# tick-ref-gps-main.net
KiCad netlist of a schematic drawn in EAGLE
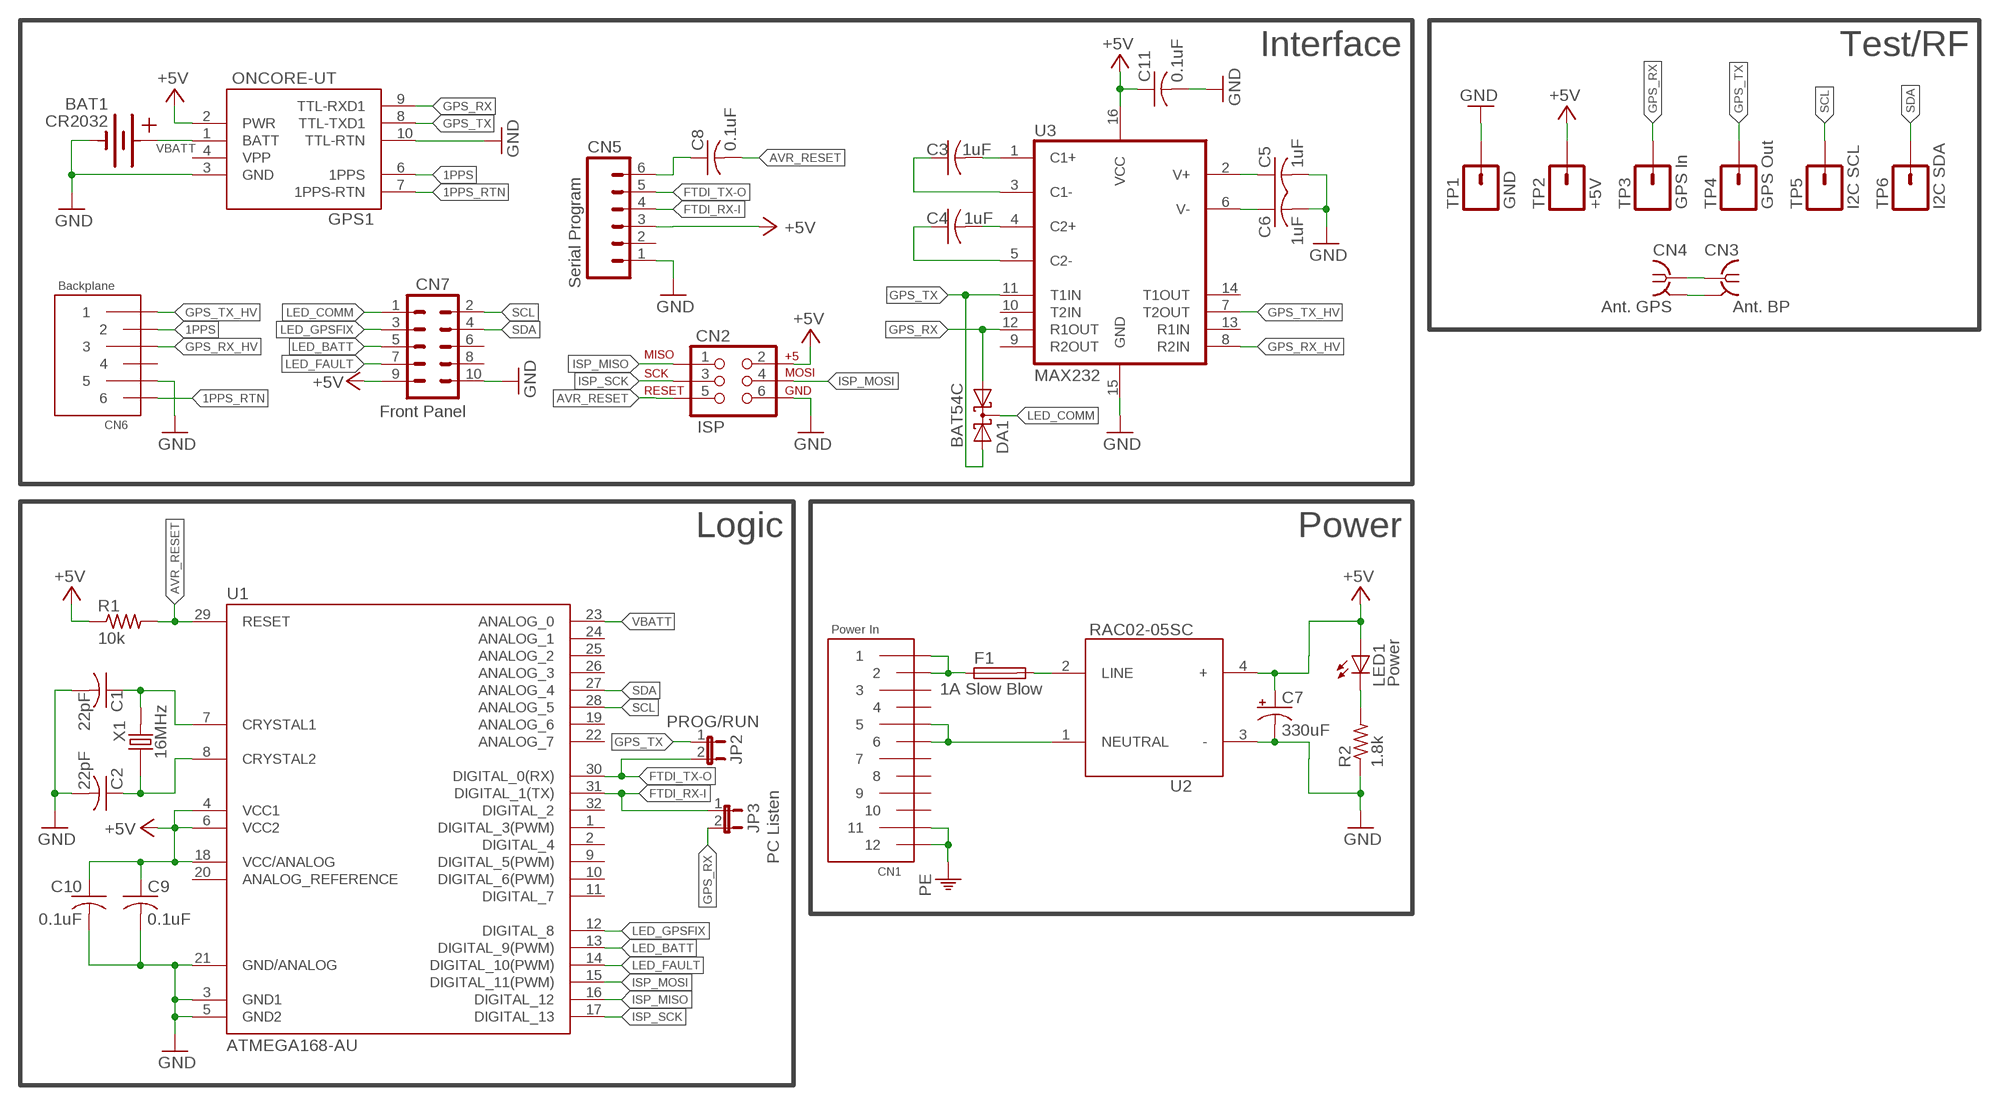
[diagram p0: schematic, sheet 1]

(export (version "E")
  (design (tool "Eeschema 10.0.6"))
  (components
    (comp (ref "BAT1")
      (value "CR2032")
      (footprint "eagle-import:BK-912-CR2032")
      (libsource (lib "eagle-import") (part "CR2032"))
    )
    (comp (ref "C1")
      (value "22pF")
      (footprint "eagle-import:C0603")
      (libsource (lib "eagle-import") (part "C-USC0603"))
    )
    (comp (ref "C2")
      (value "22pF")
      (footprint "eagle-import:C0603")
      (libsource (lib "eagle-import") (part "C-USC0603"))
    )
    (comp (ref "C3")
      (value "1uF")
      (footprint "eagle-import:C0603")
      (libsource (lib "eagle-import") (part "C-USC0603"))
    )
    (comp (ref "C4")
      (value "1uF")
      (footprint "eagle-import:C0603")
      (libsource (lib "eagle-import") (part "C-USC0603"))
    )
    (comp (ref "C5")
      (value "1uF")
      (footprint "eagle-import:C0603")
      (libsource (lib "eagle-import") (part "C-USC0603"))
    )
    (comp (ref "C6")
      (value "1uF")
      (footprint "eagle-import:C0603")
      (libsource (lib "eagle-import") (part "C-USC0603"))
    )
    (comp (ref "C7")
      (value "330uF")
      (footprint "eagle-import:E5-10,5")
      (libsource (lib "eagle-import") (part "CPOL-USE5-10.5"))
    )
    (comp (ref "C8")
      (value "0.1uF")
      (footprint "eagle-import:C0603")
      (libsource (lib "eagle-import") (part "C-USC0603"))
    )
    (comp (ref "C9")
      (value "0.1uF")
      (footprint "eagle-import:C0603")
      (libsource (lib "eagle-import") (part "C-USC0603"))
    )
    (comp (ref "C10")
      (value "0.1uF")
      (footprint "eagle-import:C0603")
      (libsource (lib "eagle-import") (part "C-USC0603"))
    )
    (comp (ref "C11")
      (value "0.1uF")
      (footprint "eagle-import:C0603")
      (libsource (lib "eagle-import") (part "C-USC0603"))
    )
    (comp (ref "CN1")
      (value "Power In")
      (footprint "eagle-import:EDGECON-M-0.15-12")
      (libsource (lib "eagle-import") (part "EDGECON-M-0.15-12"))
    )
    (comp (ref "CN2")
      (value "ISP")
      (footprint "eagle-import:2X3_LOCK")
      (libsource (lib "eagle-import") (part "AVR_SPI_PRG_62X3_LOCK"))
    )
    (comp (ref "CN3")
      (value "Ant. BP")
      (footprint "eagle-import:MMCX-J-P-X-ST-EM1-MKT")
      (libsource (lib "eagle-import") (part "COAX"))
    )
    (comp (ref "CN4")
      (value "Ant. GPS")
      (footprint "eagle-import:MOLEX-MCX-V")
      (libsource (lib "eagle-import") (part "MOLEX-MCX-V"))
    )
    (comp (ref "CN5")
      (value "Serial Program")
      (footprint "eagle-import:1X06_LOCK")
      (libsource (lib "eagle-import") (part "M06LOCK"))
    )
    (comp (ref "CN6")
      (value "Backplane")
      (footprint "eagle-import:EDGECON-M-0.1-6")
      (libsource (lib "eagle-import") (part "EDGECON-M-0.1-6"))
    )
    (comp (ref "CN7")
      (value "Front Panel")
      (footprint "eagle-import:AVR_ICSP")
      (libsource (lib "eagle-import") (part "M05X2PTH"))
    )
    (comp (ref "DA1")
      (value "BAT54C")
      (footprint "eagle-import:SOT23")
      (libsource (lib "eagle-import") (part "BAT54C"))
    )
    (comp (ref "F1")
      (value "1A Slow Blow")
      (footprint "eagle-import:SH22,5A")
      (fields (field (name "MPN") "0031.7701.11"))
      (libsource (lib "eagle-import") (part "SH22,5A"))
    )
    (comp (ref "GPS1")
      (value "ONCORE-UT")
      (footprint "eagle-import:ONCORE-UT")
      (libsource (lib "eagle-import") (part "ONCORE-UT"))
    )
    (comp (ref "JP2")
      (value "PROG/RUN")
      (footprint "eagle-import:1X02_LOCK")
      (libsource (lib "eagle-import") (part "JUMPER-2PTH_LOCK"))
    )
    (comp (ref "JP3")
      (value "PC Listen")
      (footprint "eagle-import:SJ_2S-NO")
      (libsource (lib "eagle-import") (part "JUMPER-2SMD-NO"))
    )
    (comp (ref "LED1")
      (value "Power")
      (footprint "eagle-import:CHIP-LED0603")
      (libsource (lib "eagle-import") (part "LEDCHIP-LED0603"))
    )
    (comp (ref "R1")
      (value "10k")
      (footprint "eagle-import:R0603")
      (libsource (lib "eagle-import") (part "R-US_R0603"))
    )
    (comp (ref "R2")
      (value "1.8k")
      (footprint "eagle-import:R0603")
      (libsource (lib "eagle-import") (part "R-US_R0603"))
    )
    (comp (ref "TP1")
      (value "GND")
      (footprint "eagle-import:1X01")
      (libsource (lib "eagle-import") (part "M01PTH"))
    )
    (comp (ref "TP2")
      (value "+5V")
      (footprint "eagle-import:1X01")
      (libsource (lib "eagle-import") (part "M01PTH"))
    )
    (comp (ref "TP3")
      (value "GPS In")
      (footprint "eagle-import:1X01")
      (libsource (lib "eagle-import") (part "M01PTH"))
    )
    (comp (ref "TP4")
      (value "GPS Out")
      (footprint "eagle-import:1X01")
      (libsource (lib "eagle-import") (part "M01PTH"))
    )
    (comp (ref "TP5")
      (value "I2C SCL")
      (footprint "eagle-import:1X01")
      (libsource (lib "eagle-import") (part "M01PTH"))
    )
    (comp (ref "TP6")
      (value "I2C SDA")
      (footprint "eagle-import:1X01")
      (libsource (lib "eagle-import") (part "M01PTH"))
    )
    (comp (ref "U1")
      (value "ATMEGA168-AU")
      (footprint "eagle-import:TQFP32-08")
      (libsource (lib "eagle-import") (part "ATMEGA168-AU"))
    )
    (comp (ref "U2")
      (value "RAC02-05SC")
      (footprint "eagle-import:RAC0X-SC")
      (libsource (lib "eagle-import") (part "RAC0X-SC"))
    )
    (comp (ref "U3")
      (value "MAX232")
      (footprint "eagle-import:SO016")
      (libsource (lib "eagle-import") (part "MAX232SOIC16"))
    )
    (comp (ref "X1")
      (value "16MHz")
      (footprint "eagle-import:NX5032GA")
      (libsource (lib "eagle-import") (part "NX5032GA"))
    )
  )
  (nets
    (net (code "1") (name "+5V") (class "Default")
      (node (ref "C10") (pin "1") (pinfunction "1_1") (pintype "passive"))
      (node (ref "C11") (pin "1") (pinfunction "1_1") (pintype "passive"))
      (node (ref "C7") (pin "+") (pinfunction "+_+") (pintype "passive"))
      (node (ref "C9") (pin "1") (pinfunction "1_1") (pintype "passive"))
      (node (ref "CN2") (pin "2") (pinfunction "2_2") (pintype "passive"))
      (node (ref "CN5") (pin "3") (pinfunction "3_3") (pintype "passive"))
      (node (ref "CN7") (pin "9") (pinfunction "9_9") (pintype "passive"))
      (node (ref "GPS1") (pin "2") (pinfunction "PWR_2") (pintype "power_in"))
      (node (ref "LED1") (pin "A") (pinfunction "A_A") (pintype "passive"))
      (node (ref "R1") (pin "1") (pinfunction "1_1") (pintype "passive"))
      (node (ref "TP2") (pin "1") (pinfunction "1_1") (pintype "passive"))
      (node (ref "U1") (pin "18") (pinfunction "VCC/ANALOG_18") (pintype "passive"))
      (node (ref "U1") (pin "4") (pinfunction "VCC1_4") (pintype "power_in"))
      (node (ref "U1") (pin "6") (pinfunction "VCC2_6") (pintype "power_in"))
      (node (ref "U2") (pin "4") (pinfunction "+_4") (pintype "power_in"))
      (node (ref "U3") (pin "16") (pinfunction "VCC_16") (pintype "bidirectional"))
    )
    (net (code "2") (name "/VPP") (class "Default")
      (node (ref "GPS1") (pin "4") (pinfunction "VPP_4") (pintype "power_in"))
    )
    (net (code "3") (name "1PPS") (class "Default")
      (node (ref "CN6") (pin "2") (pinfunction "2_2") (pintype "bidirectional"))
      (node (ref "GPS1") (pin "6") (pinfunction "1PPS_6") (pintype "output"))
    )
    (net (code "4") (name "1PPS_RTN") (class "Default")
      (node (ref "CN6") (pin "6") (pinfunction "6_6") (pintype "bidirectional"))
      (node (ref "GPS1") (pin "7") (pinfunction "1PPS-RTN_7") (pintype "power_in"))
    )
    (net (code "5") (name "AVR_RESET") (class "Default")
      (node (ref "C8") (pin "2") (pinfunction "2_2") (pintype "passive"))
      (node (ref "CN2") (pin "5") (pinfunction "5_5") (pintype "passive"))
      (node (ref "R1") (pin "2") (pinfunction "2_2") (pintype "passive"))
      (node (ref "U1") (pin "29") (pinfunction "RESET_29") (pintype "bidirectional"))
    )
    (net (code "6") (name "FTDI_RX-I") (class "Default")
      (node (ref "CN5") (pin "4") (pinfunction "4_4") (pintype "passive"))
      (node (ref "JP3") (pin "1") (pinfunction "1_1") (pintype "passive"))
      (node (ref "U1") (pin "31") (pinfunction "DIGITAL_1(TX)_31") (pintype "bidirectional"))
    )
    (net (code "7") (name "FTDI_TX-O") (class "Default")
      (node (ref "CN5") (pin "5") (pinfunction "5_5") (pintype "passive"))
      (node (ref "JP2") (pin "2") (pinfunction "2_2") (pintype "passive"))
      (node (ref "U1") (pin "30") (pinfunction "DIGITAL_0(RX)_30") (pintype "bidirectional"))
    )
    (net (code "8") (name "GND") (class "Default")
      (node (ref "BAT1") (pin "-") (pinfunction "-1_-") (pintype "power_in"))
      (node (ref "C1") (pin "2") (pinfunction "2_2") (pintype "passive"))
      (node (ref "C10") (pin "2") (pinfunction "2_2") (pintype "passive"))
      (node (ref "C11") (pin "2") (pinfunction "2_2") (pintype "passive"))
      (node (ref "C2") (pin "2") (pinfunction "2_2") (pintype "passive"))
      (node (ref "C5") (pin "2") (pinfunction "2_2") (pintype "passive"))
      (node (ref "C6") (pin "2") (pinfunction "2_2") (pintype "passive"))
      (node (ref "C7") (pin "-") (pinfunction "-_-") (pintype "passive"))
      (node (ref "C9") (pin "2") (pinfunction "2_2") (pintype "passive"))
      (node (ref "CN2") (pin "6") (pinfunction "6_6") (pintype "passive"))
      (node (ref "CN5") (pin "1") (pinfunction "1_1") (pintype "passive"))
      (node (ref "CN6") (pin "5") (pinfunction "5_5") (pintype "bidirectional"))
      (node (ref "CN7") (pin "10") (pinfunction "10_10") (pintype "passive"))
      (node (ref "GPS1") (pin "10") (pinfunction "TTL-RTN_10") (pintype "power_in"))
      (node (ref "GPS1") (pin "3") (pinfunction "GND_3") (pintype "power_in"))
      (node (ref "R2") (pin "1") (pinfunction "1_1") (pintype "passive"))
      (node (ref "TP1") (pin "1") (pinfunction "1_1") (pintype "passive"))
      (node (ref "U1") (pin "21") (pinfunction "GND/ANALOG_21") (pintype "power_in"))
      (node (ref "U1") (pin "3") (pinfunction "GND1_3") (pintype "power_in"))
      (node (ref "U1") (pin "5") (pinfunction "GND2_5") (pintype "power_in"))
      (node (ref "U2") (pin "3") (pinfunction "-_3") (pintype "power_in"))
      (node (ref "U3") (pin "15") (pinfunction "GND_15") (pintype "bidirectional"))
    )
    (net (code "9") (name "GPS_RX") (class "Default")
      (node (ref "DA1") (pin "1") (pinfunction "A1_1") (pintype "passive"))
      (node (ref "GPS1") (pin "9") (pinfunction "TTL-RXD1_9") (pintype "input"))
      (node (ref "JP3") (pin "2") (pinfunction "2_2") (pintype "passive"))
      (node (ref "TP3") (pin "1") (pinfunction "1_1") (pintype "passive"))
      (node (ref "U3") (pin "12") (pinfunction "R1OUT_12") (pintype "output"))
    )
    (net (code "10") (name "GPS_RX_HV") (class "Default")
      (node (ref "CN6") (pin "3") (pinfunction "3_3") (pintype "bidirectional"))
      (node (ref "U3") (pin "8") (pinfunction "R2IN_8") (pintype "input"))
    )
    (net (code "11") (name "GPS_TX") (class "Default")
      (node (ref "DA1") (pin "2") (pinfunction "A2_2") (pintype "passive"))
      (node (ref "GPS1") (pin "8") (pinfunction "TTL-TXD1_8") (pintype "output"))
      (node (ref "JP2") (pin "1") (pinfunction "1_1") (pintype "passive"))
      (node (ref "TP4") (pin "1") (pinfunction "1_1") (pintype "passive"))
      (node (ref "U3") (pin "11") (pinfunction "T1IN_11") (pintype "input"))
    )
    (net (code "12") (name "GPS_TX_HV") (class "Default")
      (node (ref "CN6") (pin "1") (pinfunction "1_1") (pintype "bidirectional"))
      (node (ref "U3") (pin "7") (pinfunction "T2OUT_7") (pintype "output"))
    )
    (net (code "13") (name "ISP_MISO") (class "Default")
      (node (ref "CN2") (pin "1") (pinfunction "1_1") (pintype "passive"))
      (node (ref "U1") (pin "16") (pinfunction "DIGITAL_12_16") (pintype "bidirectional"))
    )
    (net (code "14") (name "ISP_MOSI") (class "Default")
      (node (ref "CN2") (pin "4") (pinfunction "4_4") (pintype "passive"))
      (node (ref "U1") (pin "15") (pinfunction "DIGITAL_11(PWM)_15") (pintype "bidirectional"))
    )
    (net (code "15") (name "ISP_SCK") (class "Default")
      (node (ref "CN2") (pin "3") (pinfunction "3_3") (pintype "passive"))
      (node (ref "U1") (pin "17") (pinfunction "DIGITAL_13_17") (pintype "bidirectional"))
    )
    (net (code "16") (name "LED_BATT") (class "Default")
      (node (ref "CN7") (pin "5") (pinfunction "5_5") (pintype "passive"))
      (node (ref "U1") (pin "13") (pinfunction "DIGITAL_9(PWM)_13") (pintype "bidirectional"))
    )
    (net (code "17") (name "LED_COMM") (class "Default")
      (node (ref "CN7") (pin "1") (pinfunction "1_1") (pintype "passive"))
      (node (ref "DA1") (pin "3") (pinfunction "CC_3") (pintype "passive"))
    )
    (net (code "18") (name "LED_FAULT") (class "Default")
      (node (ref "CN7") (pin "7") (pinfunction "7_7") (pintype "passive"))
      (node (ref "U1") (pin "14") (pinfunction "DIGITAL_10(PWM)_14") (pintype "bidirectional"))
    )
    (net (code "19") (name "LED_GPSFIX") (class "Default")
      (node (ref "CN7") (pin "3") (pinfunction "3_3") (pintype "passive"))
      (node (ref "U1") (pin "12") (pinfunction "DIGITAL_8_12") (pintype "bidirectional"))
    )
    (net (code "20") (name "Net-(C8-Pad1)") (class "Default")
      (node (ref "C8") (pin "1") (pinfunction "1_1") (pintype "passive"))
      (node (ref "CN5") (pin "6") (pinfunction "6_6") (pintype "passive"))
    )
    (net (code "21") (name "Net-(CN1-Pad1)") (class "Default")
      (node (ref "CN1") (pin "1") (pinfunction "1_1") (pintype "bidirectional"))
      (node (ref "CN1") (pin "2") (pinfunction "2_2") (pintype "bidirectional"))
      (node (ref "F1") (pin "1") (pinfunction "1_1") (pintype "passive"))
    )
    (net (code "22") (name "Net-(CN3A-GND)") (class "Default")
      (node (ref "CN3") (pin "2@1") (pinfunction "GND_2@1") (pintype "power_in"))
      (node (ref "CN4") (pin "GND1") (pinfunction "GND_GND1") (pintype "passive"))
      (node (ref "CN4") (pin "GND2") (pinfunction "GND_GND2") (pintype "passive"))
      (node (ref "CN4") (pin "GND3") (pinfunction "GND_GND3") (pintype "passive"))
      (node (ref "CN4") (pin "GND4") (pinfunction "GND_GND4") (pintype "passive"))
    )
    (net (code "23") (name "Net-(CN4-A)") (class "Default")
      (node (ref "CN3") (pin "1") (pinfunction "1_1") (pintype "passive"))
      (node (ref "CN4") (pin "CTR") (pinfunction "A_CTR") (pintype "passive"))
    )
    (net (code "24") (name "Net-(LED1-PadC)") (class "Default")
      (node (ref "LED1") (pin "C") (pinfunction "C_C") (pintype "passive"))
      (node (ref "R2") (pin "2") (pinfunction "2_2") (pintype "passive"))
    )
    (net (code "25") (name "Net-(U1-CRYSTAL1)") (class "Default")
      (node (ref "C1") (pin "1") (pinfunction "1_1") (pintype "passive"))
      (node (ref "U1") (pin "7") (pinfunction "CRYSTAL1_7") (pintype "bidirectional"))
      (node (ref "X1") (pin "P$2") (pinfunction "2_P$2") (pintype "passive"))
    )
    (net (code "26") (name "Net-(U1-CRYSTAL2)") (class "Default")
      (node (ref "C2") (pin "1") (pinfunction "1_1") (pintype "passive"))
      (node (ref "U1") (pin "8") (pinfunction "CRYSTAL2_8") (pintype "bidirectional"))
      (node (ref "X1") (pin "P$1") (pinfunction "1_P$1") (pintype "passive"))
    )
    (net (code "27") (name "Net-(U2-LINE)") (class "Default")
      (node (ref "F1") (pin "2") (pinfunction "2_2") (pintype "passive"))
      (node (ref "U2") (pin "2") (pinfunction "LINE_2") (pintype "power_in"))
    )
    (net (code "28") (name "Net-(U2-NEUTRAL)") (class "Default")
      (node (ref "CN1") (pin "5") (pinfunction "5_5") (pintype "bidirectional"))
      (node (ref "CN1") (pin "6") (pinfunction "6_6") (pintype "bidirectional"))
      (node (ref "U2") (pin "1") (pinfunction "NEUTRAL_1") (pintype "power_in"))
    )
    (net (code "29") (name "Net-(U3-C1+)") (class "Default")
      (node (ref "C3") (pin "2") (pinfunction "2_2") (pintype "passive"))
      (node (ref "U3") (pin "1") (pinfunction "C1+_1") (pintype "bidirectional"))
    )
    (net (code "30") (name "Net-(U3-C1-)") (class "Default")
      (node (ref "C3") (pin "1") (pinfunction "1_1") (pintype "passive"))
      (node (ref "U3") (pin "3") (pinfunction "C1-_3") (pintype "bidirectional"))
    )
    (net (code "31") (name "Net-(U3-C2+)") (class "Default")
      (node (ref "C4") (pin "2") (pinfunction "2_2") (pintype "passive"))
      (node (ref "U3") (pin "4") (pinfunction "C2+_4") (pintype "bidirectional"))
    )
    (net (code "32") (name "Net-(U3-C2-)") (class "Default")
      (node (ref "C4") (pin "1") (pinfunction "1_1") (pintype "passive"))
      (node (ref "U3") (pin "5") (pinfunction "C2-_5") (pintype "bidirectional"))
    )
    (net (code "33") (name "Net-(U3-V+)") (class "Default")
      (node (ref "C5") (pin "1") (pinfunction "1_1") (pintype "passive"))
      (node (ref "U3") (pin "2") (pinfunction "V+_2") (pintype "bidirectional"))
    )
    (net (code "34") (name "Net-(U3-V-)") (class "Default")
      (node (ref "C6") (pin "1") (pinfunction "1_1") (pintype "passive"))
      (node (ref "U3") (pin "6") (pinfunction "V-_6") (pintype "bidirectional"))
    )
    (net (code "35") (name "PE") (class "Default")
      (node (ref "CN1") (pin "11") (pinfunction "11_11") (pintype "bidirectional"))
      (node (ref "CN1") (pin "12") (pinfunction "12_12") (pintype "bidirectional"))
    )
    (net (code "36") (name "SCL") (class "Default")
      (node (ref "CN7") (pin "2") (pinfunction "2_2") (pintype "passive"))
      (node (ref "TP5") (pin "1") (pinfunction "1_1") (pintype "passive"))
      (node (ref "U1") (pin "28") (pinfunction "ANALOG_5_28") (pintype "bidirectional"))
    )
    (net (code "37") (name "SDA") (class "Default")
      (node (ref "CN7") (pin "4") (pinfunction "4_4") (pintype "passive"))
      (node (ref "TP6") (pin "1") (pinfunction "1_1") (pintype "passive"))
      (node (ref "U1") (pin "27") (pinfunction "ANALOG_4_27") (pintype "bidirectional"))
    )
    (net (code "38") (name "VBATT") (class "Default")
      (node (ref "BAT1") (pin "+1") (pinfunction "+2_+1") (pintype "power_in"))
      (node (ref "GPS1") (pin "1") (pinfunction "BATT_1") (pintype "power_in"))
      (node (ref "U1") (pin "23") (pinfunction "ANALOG_0_23") (pintype "bidirectional"))
    )
    (net (code "39") (name "unconnected-(CN1-Pad3)") (class "Default")
      (node (ref "CN1") (pin "3") (pinfunction "3_3") (pintype "bidirectional"))
    )
    (net (code "40") (name "unconnected-(CN1-Pad4)") (class "Default")
      (node (ref "CN1") (pin "4") (pinfunction "4_4") (pintype "bidirectional"))
    )
    (net (code "41") (name "unconnected-(CN1-Pad7)") (class "Default")
      (node (ref "CN1") (pin "7") (pinfunction "7_7") (pintype "bidirectional"))
    )
    (net (code "42") (name "unconnected-(CN1-Pad8)") (class "Default")
      (node (ref "CN1") (pin "8") (pinfunction "8_8") (pintype "bidirectional"))
    )
    (net (code "43") (name "unconnected-(CN1-Pad9)") (class "Default")
      (node (ref "CN1") (pin "9") (pinfunction "9_9") (pintype "bidirectional"))
    )
    (net (code "44") (name "unconnected-(CN1-Pad10)") (class "Default")
      (node (ref "CN1") (pin "10") (pinfunction "10_10") (pintype "bidirectional"))
    )
    (net (code "45") (name "unconnected-(CN5-Pad2)") (class "Default")
      (node (ref "CN5") (pin "2") (pinfunction "2_2") (pintype "passive"))
    )
    (net (code "46") (name "unconnected-(CN6-Pad4)") (class "Default")
      (node (ref "CN6") (pin "4") (pinfunction "4_4") (pintype "bidirectional"))
    )
    (net (code "47") (name "unconnected-(CN7-Pad6)") (class "Default")
      (node (ref "CN7") (pin "6") (pinfunction "6_6") (pintype "passive"))
    )
    (net (code "48") (name "unconnected-(CN7-Pad8)") (class "Default")
      (node (ref "CN7") (pin "8") (pinfunction "8_8") (pintype "passive"))
    )
    (net (code "49") (name "unconnected-(U1-ANALOG_1-Pad24)") (class "Default")
      (node (ref "U1") (pin "24") (pinfunction "ANALOG_1_24") (pintype "bidirectional"))
    )
    (net (code "50") (name "unconnected-(U1-ANALOG_2-Pad25)") (class "Default")
      (node (ref "U1") (pin "25") (pinfunction "ANALOG_2_25") (pintype "bidirectional"))
    )
    (net (code "51") (name "unconnected-(U1-ANALOG_3-Pad26)") (class "Default")
      (node (ref "U1") (pin "26") (pinfunction "ANALOG_3_26") (pintype "bidirectional"))
    )
    (net (code "52") (name "unconnected-(U1-ANALOG_6-Pad19)") (class "Default")
      (node (ref "U1") (pin "19") (pinfunction "ANALOG_6_19") (pintype "passive"))
    )
    (net (code "53") (name "unconnected-(U1-ANALOG_7-Pad22)") (class "Default")
      (node (ref "U1") (pin "22") (pinfunction "ANALOG_7_22") (pintype "passive"))
    )
    (net (code "54") (name "unconnected-(U1-ANALOG_REFERENCE-Pad20)") (class "Default")
      (node (ref "U1") (pin "20") (pinfunction "ANALOG_REFERENCE_20") (pintype "passive"))
    )
    (net (code "55") (name "unconnected-(U1-DIGITAL_2-Pad32)") (class "Default")
      (node (ref "U1") (pin "32") (pinfunction "DIGITAL_2_32") (pintype "bidirectional"))
    )
    (net (code "56") (name "unconnected-(U1-DIGITAL_3(PWM)-Pad1)") (class "Default")
      (node (ref "U1") (pin "1") (pinfunction "DIGITAL_3(PWM)_1") (pintype "bidirectional"))
    )
    (net (code "57") (name "unconnected-(U1-DIGITAL_4-Pad2)") (class "Default")
      (node (ref "U1") (pin "2") (pinfunction "DIGITAL_4_2") (pintype "bidirectional"))
    )
    (net (code "58") (name "unconnected-(U1-DIGITAL_5(PWM)-Pad9)") (class "Default")
      (node (ref "U1") (pin "9") (pinfunction "DIGITAL_5(PWM)_9") (pintype "bidirectional"))
    )
    (net (code "59") (name "unconnected-(U1-DIGITAL_6(PWM)-Pad10)") (class "Default")
      (node (ref "U1") (pin "10") (pinfunction "DIGITAL_6(PWM)_10") (pintype "bidirectional"))
    )
    (net (code "60") (name "unconnected-(U1-DIGITAL_7-Pad11)") (class "Default")
      (node (ref "U1") (pin "11") (pinfunction "DIGITAL_7_11") (pintype "bidirectional"))
    )
    (net (code "61") (name "unconnected-(U3-R1IN-Pad13)") (class "Default")
      (node (ref "U3") (pin "13") (pinfunction "R1IN_13") (pintype "input"))
    )
    (net (code "62") (name "unconnected-(U3-R2OUT-Pad9)") (class "Default")
      (node (ref "U3") (pin "9") (pinfunction "R2OUT_9") (pintype "output"))
    )
    (net (code "63") (name "unconnected-(U3-T1OUT-Pad14)") (class "Default")
      (node (ref "U3") (pin "14") (pinfunction "T1OUT_14") (pintype "output"))
    )
    (net (code "64") (name "unconnected-(U3-T2IN-Pad10)") (class "Default")
      (node (ref "U3") (pin "10") (pinfunction "T2IN_10") (pintype "input"))
    )
  )
)
